# mag-encoder-v2.net
KiCad netlist of a schematic drawn in Altium Designer
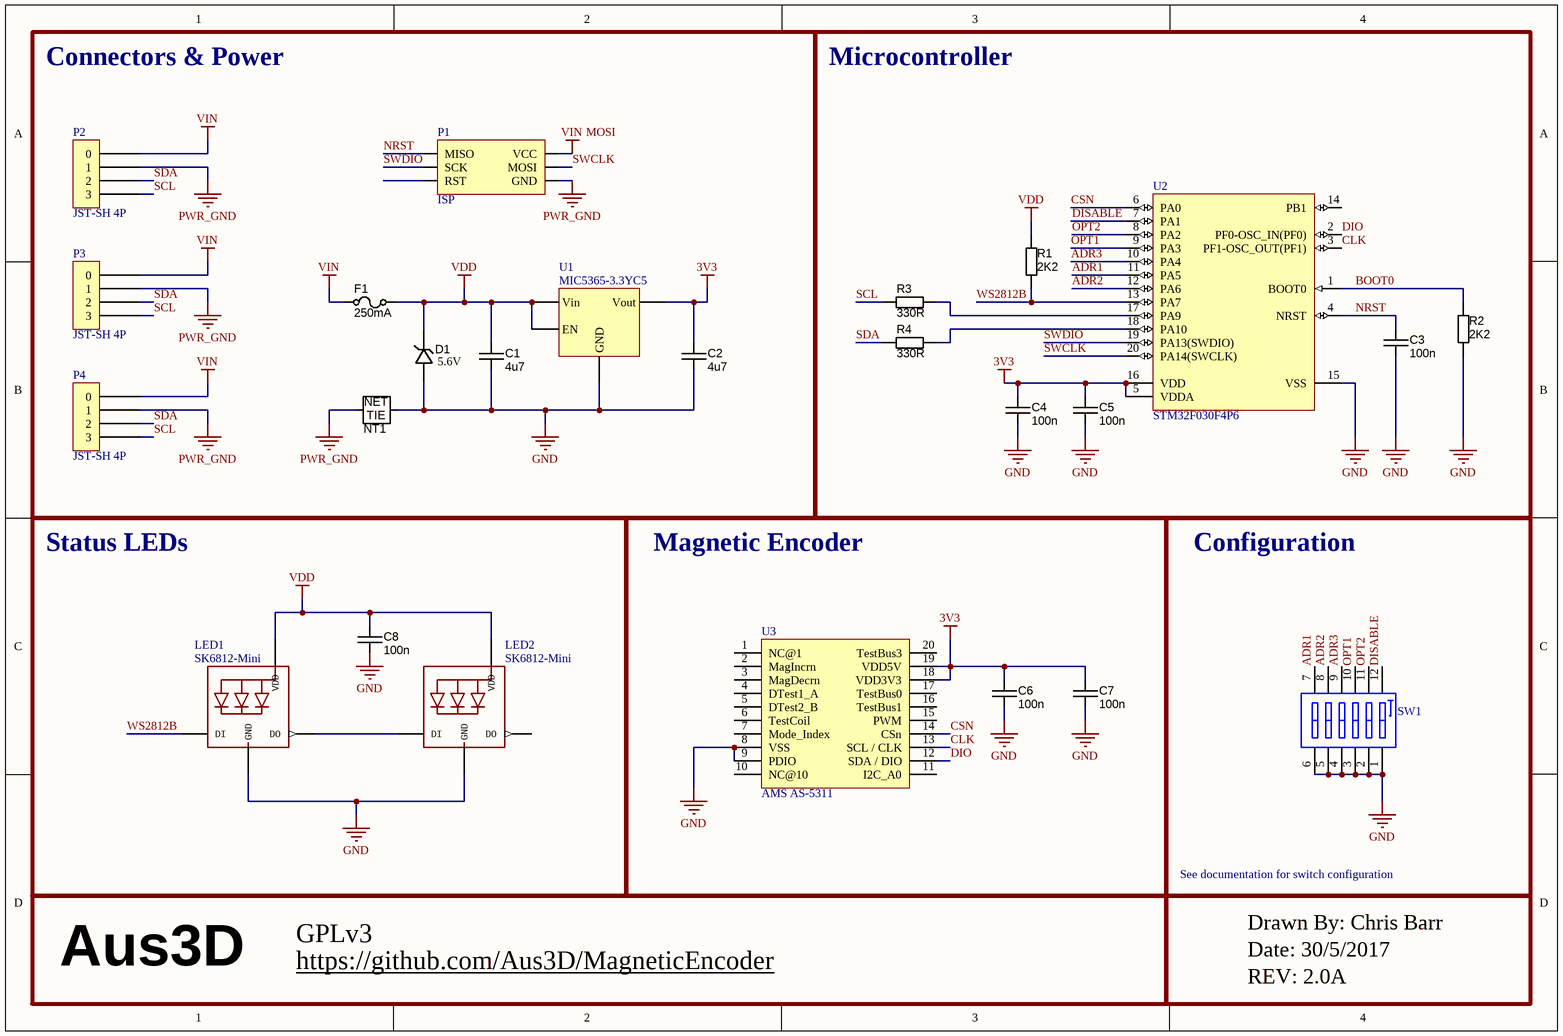
[diagram p0: mag-encoder-v2.SchDoc]

(export (version "E")
  (design (tool "Eeschema 10.0.6"))
  (components
    (comp (ref "C1")
      (value "4u7")
      (footprint "CAPC1608X90N")
      (description "Capacitor SMD Cer 4.7uF 10% 16V X5R 0603")
      (fields (field (name "TOLERANCE") "±10%") (field (name "Comment") "Approved sub OK"))
      (libsource (lib "PBL - Capacitors") (part "CAPC_100n_0603_X7R_50V_10%"))
    )
    (comp (ref "C2")
      (value "4u7")
      (footprint "CAPC1608X90N")
      (description "Capacitor SMD Cer 4.7uF 10% 16V X5R 0603")
      (fields (field (name "TOLERANCE") "±10%") (field (name "Comment") "Approved sub OK"))
      (libsource (lib "PBL - Capacitors") (part "CAPC_100n_0603_X7R_50V_10%"))
    )
    (comp (ref "C3")
      (value "100n")
      (footprint "CAPC1005X55N")
      (description "Capacitor SMD Cer 100nF 10% 16V X5R 0402")
      (fields (field (name "TOLERANCE") "±10%") (field (name "Comment") "Approved sub OK"))
      (libsource (lib "PBL - Capacitors") (part "CAPC_100n_0402_X5R_16V_10%"))
    )
    (comp (ref "C4")
      (value "100n")
      (footprint "CAPC1005X55N")
      (description "Capacitor SMD Cer 100nF 10% 16V X5R 0402")
      (fields (field (name "TOLERANCE") "±10%") (field (name "Comment") "Approved sub OK"))
      (libsource (lib "PBL - Capacitors") (part "CAPC_100n_0402_X5R_16V_10%"))
    )
    (comp (ref "C5")
      (value "100n")
      (footprint "CAPC1005X55N")
      (description "Capacitor SMD Cer 100nF 10% 16V X5R 0402")
      (fields (field (name "TOLERANCE") "±10%") (field (name "Comment") "Approved sub OK"))
      (libsource (lib "PBL - Capacitors") (part "CAPC_100n_0402_X5R_16V_10%"))
    )
    (comp (ref "C6")
      (value "100n")
      (footprint "CAPC1005X55N")
      (description "Capacitor SMD Cer 100nF 10% 16V X5R 0402")
      (fields (field (name "TOLERANCE") "±10%") (field (name "Comment") "Approved sub OK"))
      (libsource (lib "PBL - Capacitors") (part "CAPC_100n_0402_X5R_16V_10%"))
    )
    (comp (ref "C7")
      (value "100n")
      (footprint "CAPC1005X55N")
      (description "Capacitor SMD Cer 100nF 10% 16V X5R 0402")
      (fields (field (name "TOLERANCE") "±10%") (field (name "Comment") "Approved sub OK"))
      (libsource (lib "PBL - Capacitors") (part "CAPC_100n_0402_X5R_16V_10%"))
    )
    (comp (ref "C8")
      (value "100n")
      (footprint "CAPC1005X55N")
      (description "Capacitor SMD Cer 100nF 10% 16V X5R 0402")
      (fields (field (name "TOLERANCE") "±10%") (field (name "Comment") "Approved sub OK"))
      (libsource (lib "PBL - Capacitors") (part "CAPC_100n_0402_X5R_16V_10%"))
    )
    (comp (ref "D1")
      (value "5.6V")
      (footprint "SOD123")
      (description "Diode Zener SMD 5.6V 0.5W SOD-123 BZT52C5V6")
      (fields (field (name "TOLERANCE") "±7%") (field (name "Comment") "Approved sub OK"))
      (libsource (lib "Schlib1") (part "DIODE_ZENER_5.6V_500mW"))
    )
    (comp (ref "F1")
      (value "250mA")
      (footprint "PTC Fuse1608-0603")
      (description "Fuse - 15V 100mA Hold 250mA Trip PTC SMD 0603")
      (fields (field (name "Comment") "Approved sub OK"))
      (libsource (lib "Schlib1") (part "Fuse - 15V 100mA Hold 250mA Trip PTC SMD 0603"))
    )
    (comp (ref "LED1")
      (value "SK6812-Mini")
      (footprint "SK6812")
      (description "RGB Smart LED WS2812 / SK6812 Mini 3535")
      (libsource (lib "adafruit") (part "WS2812B3535"))
    )
    (comp (ref "LED2")
      (value "SK6812-Mini")
      (footprint "SK6812")
      (description "RGB Smart LED WS2812 / SK6812 Mini 3535")
      (libsource (lib "adafruit") (part "WS2812B3535"))
    )
    (comp (ref "NT1")
      (value "Net Tie")
      (footprint "NetTie_Internal2_24mil")
      (libsource (lib "PBL - Pads and Jumpers") (part "JUMP_NETTIE"))
    )
    (comp (ref "P1")
      (value "ISP")
      (footprint "ICSP Pads - SMD")
      (libsource (lib "Schlib1") (part "ISP Header"))
    )
    (comp (ref "P2")
      (value "JST-SH 4P")
      (footprint "SM04B-SRSS-TB")
      (description "JST SH 4P Connector")
      (libsource (lib "Schlib1") (part "SM04B-SRSS-TB"))
    )
    (comp (ref "P3")
      (value "JST-SH 4P")
      (footprint "SM04B-SRSS-TB")
      (description "JST SH 4P Connector")
      (libsource (lib "Schlib1") (part "SM04B-SRSS-TB"))
    )
    (comp (ref "P4")
      (value "JST-SH 4P")
      (footprint "SM04B-SRSS-TB")
      (description "JST SH 4P Connector")
      (libsource (lib "Schlib1") (part "SM04B-SRSS-TB"))
    )
    (comp (ref "R1")
      (value "2K2")
      (footprint "RESC1005X40N")
      (description "Resistor SMD chip 2.2k Ohm 0.063W 5% 0402")
      (fields (field (name "TOLERANCE") "±5%") (field (name "Comment") "Approved sub OK"))
      (libsource (lib "PBL - Resistors") (part "RES_2K2_0402_5%"))
    )
    (comp (ref "R2")
      (value "2K2")
      (footprint "RESC1005X40N")
      (description "Resistor SMD chip 2.2k Ohm 0.063W 5% 0402")
      (fields (field (name "TOLERANCE") "±5%") (field (name "Comment") "Approved sub OK"))
      (libsource (lib "PBL - Resistors") (part "RES_2K2_0402_5%"))
    )
    (comp (ref "R3")
      (value "330R")
      (footprint "RESC1005X40N")
      (description "Resistor SMD chip 330 Ohm 0.063W 5% 0402")
      (fields (field (name "TOLERANCE") "±5%") (field (name "Comment") "Approved sub OK"))
      (libsource (lib "PBL - Resistors") (part "RES_330R_0402_5%"))
    )
    (comp (ref "R4")
      (value "330R")
      (footprint "RESC1005X40N")
      (description "Resistor SMD chip 330 Ohm 0.063W 5% 0402")
      (fields (field (name "TOLERANCE") "±5%") (field (name "Comment") "Approved sub OK"))
      (libsource (lib "PBL - Resistors") (part "RES_330R_0402_5%"))
    )
    (comp (ref "SW1")
      (value "Approved sub OK")
      (footprint "DIPSW SMD 6 Way")
      (description "SMD DIP Switch 1.27mm Pitch 6 Position")
      (fields (field (name "PUBLISHER") "Altium Limited"))
      (libsource (lib "Schlib1") (part "SW DIP-6"))
    )
    (comp (ref "U1")
      (value "MIC5365-3.3YC5")
      (footprint "SC70-5")
      (description "3.3V LDO Regulator")
      (libsource (lib "Schlib1") (part "Regulator - MIC5365 3.3V Linear Regulator"))
    )
    (comp (ref "U2")
      (value "STM32F030F4P6")
      (footprint "STM-TSSOP20_N")
      (libsource (lib "STMicroelectronics STM32 F0") (part "STM32F030F4P6"))
    )
    (comp (ref "U3")
      (value "AMS AS-5311")
      (footprint "NSE-5310")
      (description "AMS Linear Magnetic Encoder IC")
      (libsource (lib "Schlib1") (part "AMS AS-5311"))
    )
  )
  (nets
    (net (code "1") (name "/ADR1") (class "Default")
      (node (ref "SW1") (pin "7") (pinfunction "7_7") (pintype "passive"))
      (node (ref "U2") (pin "11") (pinfunction "PA5_11") (pintype "bidirectional"))
    )
    (net (code "2") (name "/ADR2") (class "Default")
      (node (ref "SW1") (pin "8") (pinfunction "8_8") (pintype "passive"))
      (node (ref "U2") (pin "12") (pinfunction "PA6_12") (pintype "bidirectional"))
    )
    (net (code "3") (name "/ADR3") (class "Default")
      (node (ref "SW1") (pin "9") (pinfunction "9_9") (pintype "passive"))
      (node (ref "U2") (pin "10") (pinfunction "PA4_10") (pintype "bidirectional"))
    )
    (net (code "4") (name "/BOOT0") (class "Default")
      (node (ref "R2") (pin "1") (pinfunction "1_1") (pintype "passive"))
      (node (ref "U2") (pin "1") (pinfunction "BOOT0_1") (pintype "input"))
    )
    (net (code "5") (name "/CLK") (class "Default")
      (node (ref "U2") (pin "3") (pinfunction "PF1-OSC_OUT(PF1)_3") (pintype "bidirectional"))
      (node (ref "U3") (pin "13") (pinfunction "SCL_/_CLK_13") (pintype "passive"))
    )
    (net (code "6") (name "/CSN") (class "Default")
      (node (ref "U2") (pin "6") (pinfunction "PA0_6") (pintype "bidirectional"))
      (node (ref "U3") (pin "14") (pinfunction "CSn_14") (pintype "passive"))
    )
    (net (code "7") (name "/DIO") (class "Default")
      (node (ref "U2") (pin "2") (pinfunction "PF0-OSC_IN(PF0)_2") (pintype "bidirectional"))
      (node (ref "U3") (pin "12") (pinfunction "SDA_/_DIO_12") (pintype "passive"))
    )
    (net (code "8") (name "/DISABLE") (class "Default")
      (node (ref "SW1") (pin "12") (pinfunction "12_12") (pintype "passive"))
      (node (ref "U2") (pin "7") (pinfunction "PA1_7") (pintype "bidirectional"))
    )
    (net (code "10") (name "/NRST") (class "Default")
      (node (ref "C3") (pin "1") (pintype "passive"))
      (node (ref "P1") (pin "0") (pinfunction "MISO_0") (pintype "passive"))
      (node (ref "U2") (pin "4") (pinfunction "NRST_4") (pintype "bidirectional"))
    )
    (net (code "11") (name "/OPT1") (class "Default")
      (node (ref "SW1") (pin "10") (pinfunction "10_10") (pintype "passive"))
      (node (ref "U2") (pin "9") (pinfunction "PA3_9") (pintype "bidirectional"))
    )
    (net (code "12") (name "/OPT2") (class "Default")
      (node (ref "SW1") (pin "11") (pinfunction "11_11") (pintype "passive"))
      (node (ref "U2") (pin "8") (pinfunction "PA2_8") (pintype "bidirectional"))
    )
    (net (code "13") (name "/SCL") (class "Default")
      (node (ref "P2") (pin "3") (pinfunction "3_3") (pintype "passive"))
      (node (ref "P3") (pin "3") (pinfunction "3_3") (pintype "passive"))
      (node (ref "P4") (pin "3") (pinfunction "3_3") (pintype "passive"))
      (node (ref "R3") (pin "1") (pinfunction "1_1") (pintype "passive"))
    )
    (net (code "14") (name "/SDA") (class "Default")
      (node (ref "P2") (pin "2") (pinfunction "2_2") (pintype "passive"))
      (node (ref "P3") (pin "2") (pinfunction "2_2") (pintype "passive"))
      (node (ref "P4") (pin "2") (pinfunction "2_2") (pintype "passive"))
      (node (ref "R4") (pin "1") (pinfunction "1_1") (pintype "passive"))
    )
    (net (code "15") (name "/SWCLK") (class "Default")
      (node (ref "P1") (pin "3") (pinfunction "MOSI_3") (pintype "passive"))
      (node (ref "U2") (pin "20") (pinfunction "PA14(SWCLK)_20") (pintype "bidirectional"))
    )
    (net (code "16") (name "/SWDIO") (class "Default")
      (node (ref "P1") (pin "2") (pinfunction "SCK_2") (pintype "passive"))
      (node (ref "U2") (pin "19") (pinfunction "PA13(SWDIO)_19") (pintype "bidirectional"))
    )
    (net (code "17") (name "/WS2812B") (class "Default")
      (node (ref "LED1") (pin "1") (pinfunction "DI_1") (pintype "passive"))
      (node (ref "R1") (pin "2") (pinfunction "2_2") (pintype "passive"))
      (node (ref "U2") (pin "13") (pinfunction "PA7_13") (pintype "bidirectional"))
    )
    (net (code "18") (name "3V3") (class "Default")
      (node (ref "C2") (pin "1") (pintype "passive"))
      (node (ref "C4") (pin "1") (pintype "passive"))
      (node (ref "C5") (pin "1") (pintype "passive"))
      (node (ref "C6") (pin "1") (pintype "passive"))
      (node (ref "C7") (pin "1") (pintype "passive"))
      (node (ref "U1") (pin "5") (pinfunction "Vout_5") (pintype "passive"))
      (node (ref "U2") (pin "16") (pinfunction "VDD_16") (pintype "power_in"))
      (node (ref "U2") (pin "5") (pinfunction "VDDA_5") (pintype "power_in"))
      (node (ref "U3") (pin "18") (pinfunction "VDD3V3_18") (pintype "passive"))
      (node (ref "U3") (pin "19") (pinfunction "VDD5V_19") (pintype "passive"))
    )
    (net (code "19") (name "GND") (class "Default")
      (node (ref "C1") (pin "2") (pintype "passive"))
      (node (ref "C2") (pin "2") (pintype "passive"))
      (node (ref "C3") (pin "2") (pintype "passive"))
      (node (ref "C4") (pin "2") (pintype "passive"))
      (node (ref "C5") (pin "2") (pintype "passive"))
      (node (ref "C6") (pin "2") (pintype "passive"))
      (node (ref "C7") (pin "2") (pintype "passive"))
      (node (ref "C8") (pin "2") (pintype "passive"))
      (node (ref "D1") (pin "A") (pinfunction "A_A") (pintype "passive"))
      (node (ref "LED1") (pin "4") (pinfunction "GND_4") (pintype "power_in"))
      (node (ref "LED2") (pin "4") (pinfunction "GND_4") (pintype "power_in"))
      (node (ref "NT1") (pin "2") (pinfunction "2_2") (pintype "passive"))
      (node (ref "R2") (pin "2") (pinfunction "2_2") (pintype "passive"))
      (node (ref "SW1") (pin "1") (pinfunction "A1_1") (pintype "passive"))
      (node (ref "SW1") (pin "2") (pinfunction "A2_2") (pintype "passive"))
      (node (ref "SW1") (pin "3") (pinfunction "A3_3") (pintype "passive"))
      (node (ref "SW1") (pin "4") (pinfunction "4_4") (pintype "passive"))
      (node (ref "SW1") (pin "5") (pinfunction "5_5") (pintype "passive"))
      (node (ref "SW1") (pin "6") (pinfunction "6_6") (pintype "passive"))
      (node (ref "U1") (pin "2") (pinfunction "GND_2") (pintype "passive"))
      (node (ref "U2") (pin "15") (pinfunction "VSS_15") (pintype "power_in"))
      (node (ref "U3") (pin "8") (pinfunction "VSS_8") (pintype "passive"))
      (node (ref "U3") (pin "9") (pinfunction "PDIO_9") (pintype "passive"))
    )
    (net (code "20") (name "Net-(LED1-DO)") (class "Default")
      (node (ref "LED1") (pin "3") (pinfunction "DO_3") (pintype "output"))
      (node (ref "LED2") (pin "1") (pinfunction "DI_1") (pintype "passive"))
    )
    (net (code "21") (name "Net-(U2-PA9)") (class "Default")
      (node (ref "R3") (pin "2") (pinfunction "2_2") (pintype "passive"))
      (node (ref "U2") (pin "17") (pinfunction "PA9_17") (pintype "bidirectional"))
    )
    (net (code "22") (name "Net-(U2-PA10)") (class "Default")
      (node (ref "R4") (pin "2") (pinfunction "2_2") (pintype "passive"))
      (node (ref "U2") (pin "18") (pinfunction "PA10_18") (pintype "bidirectional"))
    )
    (net (code "23") (name "PWR_GND") (class "Default")
      (node (ref "NT1") (pin "1") (pinfunction "1_1") (pintype "passive"))
      (node (ref "P1") (pin "5") (pinfunction "GND_5") (pintype "passive"))
      (node (ref "P2") (pin "1") (pinfunction "1_1") (pintype "passive"))
      (node (ref "P3") (pin "1") (pinfunction "1_1") (pintype "passive"))
      (node (ref "P4") (pin "1") (pinfunction "1_1") (pintype "passive"))
    )
    (net (code "24") (name "VDD") (class "Default")
      (node (ref "C1") (pin "1") (pintype "passive"))
      (node (ref "C8") (pin "1") (pintype "passive"))
      (node (ref "D1") (pin "K") (pinfunction "K_K") (pintype "passive"))
      (node (ref "F1") (pin "2") (pinfunction "2_2") (pintype "passive"))
      (node (ref "LED1") (pin "2") (pinfunction "VDD_2") (pintype "power_in"))
      (node (ref "LED2") (pin "2") (pinfunction "VDD_2") (pintype "power_in"))
      (node (ref "R1") (pin "1") (pinfunction "1_1") (pintype "passive"))
      (node (ref "U1") (pin "1") (pinfunction "Vin_1") (pintype "passive"))
      (node (ref "U1") (pin "3") (pinfunction "EN_3") (pintype "passive"))
    )
    (net (code "25") (name "VIN") (class "Default")
      (node (ref "F1") (pin "1") (pinfunction "1_1") (pintype "passive"))
      (node (ref "P1") (pin "1") (pinfunction "VCC_1") (pintype "passive"))
      (node (ref "P2") (pin "0") (pinfunction "0_0") (pintype "passive"))
      (node (ref "P3") (pin "0") (pinfunction "0_0") (pintype "passive"))
      (node (ref "P4") (pin "0") (pinfunction "0_0") (pintype "passive"))
    )
    (net (code "26") (name "unconnected-(LED2-DO-Pad3)") (class "Default")
      (node (ref "LED2") (pin "3") (pinfunction "DO_3") (pintype "output"))
    )
    (net (code "27") (name "unconnected-(P1-RST-Pad4)") (class "Default")
      (node (ref "P1") (pin "4") (pinfunction "RST_4") (pintype "passive"))
    )
    (net (code "28") (name "unconnected-(U2-PB1-Pad14)") (class "Default")
      (node (ref "U2") (pin "14") (pinfunction "PB1_14") (pintype "bidirectional"))
    )
    (net (code "29") (name "unconnected-(U3-DTest1_A-Pad4)") (class "Default")
      (node (ref "U3") (pin "4") (pinfunction "DTest1_A_4") (pintype "passive"))
    )
    (net (code "30") (name "unconnected-(U3-DTest2_B-Pad5)") (class "Default")
      (node (ref "U3") (pin "5") (pinfunction "DTest2_B_5") (pintype "passive"))
    )
    (net (code "31") (name "unconnected-(U3-I2C_A0-Pad11)") (class "Default")
      (node (ref "U3") (pin "11") (pinfunction "I2C_A0_11") (pintype "passive"))
    )
    (net (code "32") (name "unconnected-(U3-MagDecrn-Pad3)") (class "Default")
      (node (ref "U3") (pin "3") (pinfunction "MagDecrn_3") (pintype "passive"))
    )
    (net (code "33") (name "unconnected-(U3-MagIncrn-Pad2)") (class "Default")
      (node (ref "U3") (pin "2") (pinfunction "MagIncrn_2") (pintype "passive"))
    )
    (net (code "34") (name "unconnected-(U3-Mode_Index-Pad7)") (class "Default")
      (node (ref "U3") (pin "7") (pinfunction "Mode_Index_7") (pintype "passive"))
    )
    (net (code "35") (name "unconnected-(U3-NC@1-Pad1)") (class "Default")
      (node (ref "U3") (pin "1") (pinfunction "NC@1_1") (pintype "passive"))
    )
    (net (code "36") (name "unconnected-(U3-NC@10-Pad10)") (class "Default")
      (node (ref "U3") (pin "10") (pinfunction "NC@10_10") (pintype "passive"))
    )
    (net (code "37") (name "unconnected-(U3-PWM-Pad15)") (class "Default")
      (node (ref "U3") (pin "15") (pinfunction "PWM_15") (pintype "passive"))
    )
    (net (code "38") (name "unconnected-(U3-TestBus0-Pad17)") (class "Default")
      (node (ref "U3") (pin "17") (pinfunction "TestBus0_17") (pintype "passive"))
    )
    (net (code "39") (name "unconnected-(U3-TestBus1-Pad16)") (class "Default")
      (node (ref "U3") (pin "16") (pinfunction "TestBus1_16") (pintype "passive"))
    )
    (net (code "40") (name "unconnected-(U3-TestBus3-Pad20)") (class "Default")
      (node (ref "U3") (pin "20") (pinfunction "TestBus3_20") (pintype "passive"))
    )
    (net (code "41") (name "unconnected-(U3-TestCoil-Pad6)") (class "Default")
      (node (ref "U3") (pin "6") (pinfunction "TestCoil_6") (pintype "passive"))
    )
  )
)
